# QVAR.net
KiCad netlist of a schematic drawn in Altium Designer
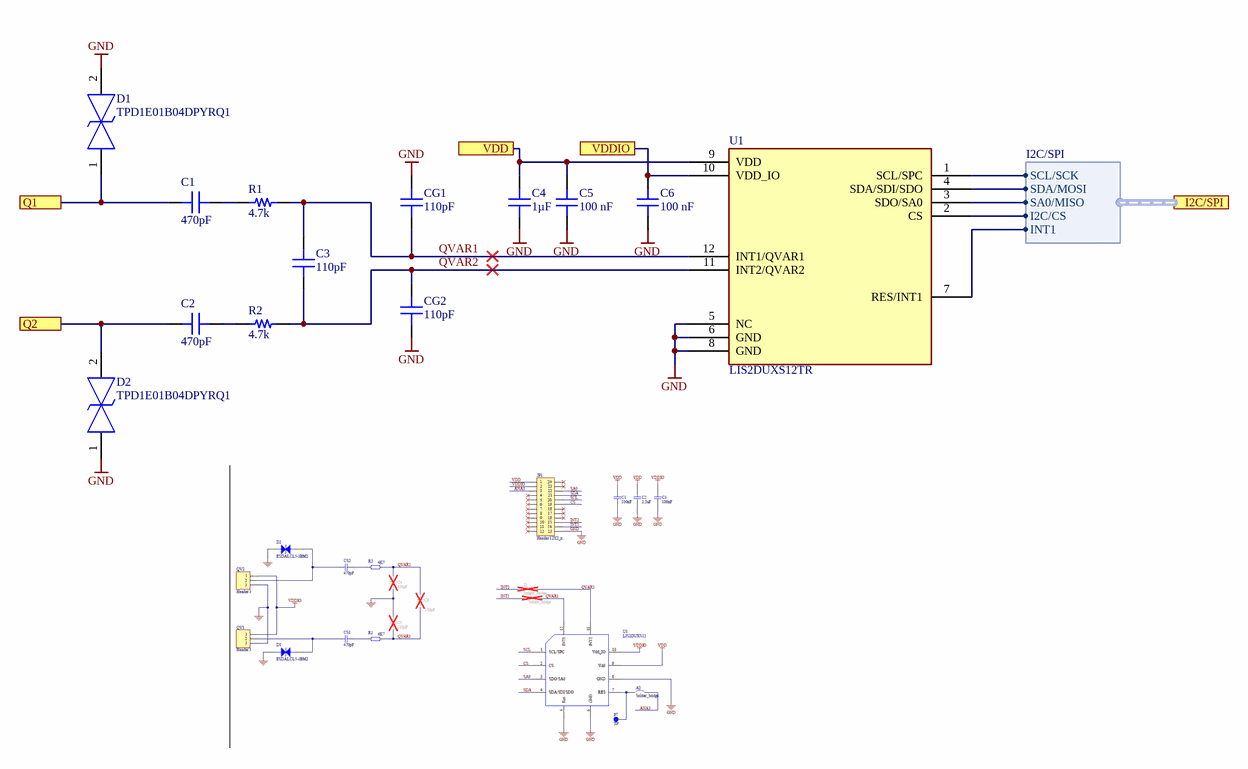
[diagram p0: QVAR.SchDoc]

(export (version "E")
  (design (tool "Eeschema 10.0.6"))
  (components
    (comp (ref "C1")
      (value "470pF")
      (footprint "CAP_0201")
      (description "CAP CER 470PF 25V C0G 0201")
      (fields
        (field (name "MANUFACTURER") "Murata")
        (field (name "MANUFACTURER PART NUMBER") "GRM0335C1E471JA01D")
      )
      (libsource (lib "6QChan_vitalcore_backpack") (part "CAP_0201_470p_25V"))
    )
    (comp (ref "C2")
      (value "470pF")
      (footprint "CAP_0201")
      (description "CAP CER 470PF 25V C0G 0201")
      (fields
        (field (name "MANUFACTURER") "Murata")
        (field (name "MANUFACTURER PART NUMBER") "GRM0335C1E471JA01D")
      )
      (libsource (lib "6QChan_vitalcore_backpack") (part "CAP_0201_470p_25V"))
    )
    (comp (ref "C3")
      (value "110pF")
      (footprint "CAP_0201")
      (description "CAP CER 110PF 50V C0G 0201")
      (fields
        (field (name "MANUFACTURER") "Murata")
        (field (name "MANUFACTURER PART NUMBER") "GRM0335C1H111JA01D")
      )
      (libsource (lib "6QChan_vitalcore_backpack") (part "CAP_0201_110p_50V"))
    )
    (comp (ref "C4")
      (value "1µF")
      (footprint "CAP_0201")
      (description "CAP CER 1UF 10V X6S")
      (fields
        (field (name "MANUFACTURER") "Murata")
        (field (name "MANUFACTURER PART NUMBER") "GRM033C81A105ME05D")
      )
      (libsource (lib "6QChan_vitalcore_backpack") (part "CAP_0201_1u_10V"))
    )
    (comp (ref "C5")
      (value "100 nF")
      (footprint "CAP_0201")
      (description "CAP CER 0.1UF 25V X5R 0201")
      (fields
        (field (name "MANUFACTURER") "Murata")
        (field (name "MANUFACTURER PART NUMBER") "GRM033R6YA104ME14D")
      )
      (libsource (lib "6QChan_vitalcore_backpack") (part "CAP_0201_100n_10V"))
    )
    (comp (ref "C6")
      (value "100 nF")
      (footprint "CAP_0201")
      (description "CAP CER 0.1UF 25V X5R 0201")
      (fields
        (field (name "MANUFACTURER") "Murata")
        (field (name "MANUFACTURER PART NUMBER") "GRM033R6YA104ME14D")
      )
      (libsource (lib "6QChan_vitalcore_backpack") (part "CAP_0201_100n_10V"))
    )
    (comp (ref "CG1")
      (value "110pF")
      (footprint "CAP_0201")
      (description "CAP CER 110PF 50V C0G 0201")
      (fields
        (field (name "MANUFACTURER") "Murata")
        (field (name "MANUFACTURER PART NUMBER") "GRM0335C1H111JA01D")
      )
      (libsource (lib "6QChan_vitalcore_backpack") (part "CAP_0201_110p_50V"))
    )
    (comp (ref "CG2")
      (value "110pF")
      (footprint "CAP_0201")
      (description "CAP CER 110PF 50V C0G 0201")
      (fields
        (field (name "MANUFACTURER") "Murata")
        (field (name "MANUFACTURER PART NUMBER") "GRM0335C1H111JA01D")
      )
      (libsource (lib "6QChan_vitalcore_backpack") (part "CAP_0201_110p_50V"))
    )
    (comp (ref "D1")
      (value "TPD1E01B04DPYRQ1")
      (footprint "TPD1E01B04DPYRQ1")
      (description "TVS Diode (Bi-directional)")
      (fields (field (name "MANUFACTURER") "Texas Instruments"))
      (libsource (lib "6QChan_vitalcore_backpack") (part "TPD1E01B04DPYRQ1"))
    )
    (comp (ref "D2")
      (value "TPD1E01B04DPYRQ1")
      (footprint "TPD1E01B04DPYRQ1")
      (description "TVS Diode (Bi-directional)")
      (fields (field (name "MANUFACTURER") "Texas Instruments"))
      (libsource (lib "6QChan_vitalcore_backpack") (part "TPD1E01B04DPYRQ1"))
    )
    (comp (ref "R1")
      (value "4.7k")
      (footprint "RES_0201")
      (description "R 4.7K 1% 50mW 0201")
      (fields
        (field (name "MANUFACTURER") "Panasonic")
        (field (name "MANUFACTURER PART NUMBER") "ERJ-1GNF4701C")
      )
      (libsource (lib "6QChan_vitalcore_backpack") (part "R_0201_4.7K"))
    )
    (comp (ref "R2")
      (value "4.7k")
      (footprint "RES_0201")
      (description "R 4.7K 1% 50mW 0201")
      (fields
        (field (name "MANUFACTURER") "Panasonic")
        (field (name "MANUFACTURER PART NUMBER") "ERJ-1GNF4701C")
      )
      (libsource (lib "6QChan_vitalcore_backpack") (part "R_0201_4.7K"))
    )
    (comp (ref "U1")
      (value "LIS2DUXS12TR")
      (footprint "QFN_DUXS12_STM-M")
      (description "IC IMU QVAR")
      (fields (field (name "MANUFACTURER") "STMicroelectronics"))
      (libsource (lib "6QChan_vitalcore_backpack") (part "LIS2DUXS12TR"))
    )
  )
  (nets
    (net (code "2") (name "/I2C{slash}CS") (class "Default")
      (node (ref "U1") (pin "2") (pinfunction "CS_2") (pintype "passive"))
    )
    (net (code "3") (name "/INT1") (class "Default")
      (node (ref "U1") (pin "7") (pinfunction "RES/INT1_7") (pintype "passive"))
    )
    (net (code "4") (name "/Q1") (class "Default")
      (node (ref "C1") (pin "1") (pinfunction "1_1") (pintype "passive"))
      (node (ref "D1") (pin "1") (pinfunction "1_1") (pintype "passive"))
    )
    (net (code "5") (name "/Q2") (class "Default")
      (node (ref "C2") (pin "1") (pinfunction "1_1") (pintype "passive"))
      (node (ref "D2") (pin "2") (pinfunction "2_2") (pintype "passive"))
    )
    (net (code "6") (name "/QVAR1") (class "Default")
      (node (ref "C3") (pin "1") (pinfunction "1_1") (pintype "passive"))
      (node (ref "CG1") (pin "2") (pinfunction "2_2") (pintype "passive"))
      (node (ref "R1") (pin "2") (pinfunction "2_2") (pintype "passive"))
      (node (ref "U1") (pin "12") (pinfunction "INT1/QVAR1_12") (pintype "passive"))
    )
    (net (code "7") (name "/QVAR2") (class "Default")
      (node (ref "C3") (pin "2") (pinfunction "2_2") (pintype "passive"))
      (node (ref "CG2") (pin "2") (pinfunction "2_2") (pintype "passive"))
      (node (ref "R2") (pin "2") (pinfunction "2_2") (pintype "passive"))
      (node (ref "U1") (pin "11") (pinfunction "INT2/QVAR2_11") (pintype "passive"))
    )
    (net (code "8") (name "/SA0{slash}MISO") (class "Default")
      (node (ref "U1") (pin "3") (pinfunction "SDO/SA0_3") (pintype "passive"))
    )
    (net (code "9") (name "/SCL{slash}SCK") (class "Default")
      (node (ref "U1") (pin "1") (pinfunction "SCL/SPC_1") (pintype "passive"))
    )
    (net (code "10") (name "/SDA{slash}MOSI") (class "Default")
      (node (ref "U1") (pin "4") (pinfunction "SDA/SDI/SDO_4") (pintype "passive"))
    )
    (net (code "11") (name "/VDD") (class "Default")
      (node (ref "C4") (pin "1") (pinfunction "1_1") (pintype "passive"))
      (node (ref "C5") (pin "2") (pinfunction "2_2") (pintype "passive"))
      (node (ref "U1") (pin "9") (pinfunction "VDD_9") (pintype "power_in"))
    )
    (net (code "12") (name "/VDDIO") (class "Default")
      (node (ref "C6") (pin "2") (pinfunction "2_2") (pintype "passive"))
      (node (ref "U1") (pin "10") (pinfunction "VDD_IO_10") (pintype "power_in"))
    )
    (net (code "14") (name "GND") (class "Default")
      (node (ref "C4") (pin "2") (pinfunction "2_2") (pintype "passive"))
      (node (ref "C5") (pin "1") (pinfunction "1_1") (pintype "passive"))
      (node (ref "C6") (pin "1") (pinfunction "1_1") (pintype "passive"))
      (node (ref "CG1") (pin "1") (pinfunction "1_1") (pintype "passive"))
      (node (ref "CG2") (pin "1") (pinfunction "1_1") (pintype "passive"))
      (node (ref "D1") (pin "2") (pinfunction "2_2") (pintype "passive"))
      (node (ref "D2") (pin "1") (pinfunction "1_1") (pintype "passive"))
      (node (ref "U1") (pin "5") (pinfunction "NC_5") (pintype "passive"))
      (node (ref "U1") (pin "6") (pinfunction "GND_6") (pintype "power_in"))
      (node (ref "U1") (pin "8") (pinfunction "GND_8") (pintype "power_in"))
    )
    (net (code "15") (name "Net-(C1-Pad2)") (class "Default")
      (node (ref "C1") (pin "2") (pinfunction "2_2") (pintype "passive"))
      (node (ref "R1") (pin "1") (pinfunction "1_1") (pintype "passive"))
    )
    (net (code "16") (name "Net-(C2-Pad2)") (class "Default")
      (node (ref "C2") (pin "2") (pinfunction "2_2") (pintype "passive"))
      (node (ref "R2") (pin "1") (pinfunction "1_1") (pintype "passive"))
    )
  )
)
